# PR9025_B.net
KiCad netlist of a schematic drawn in EAGLE
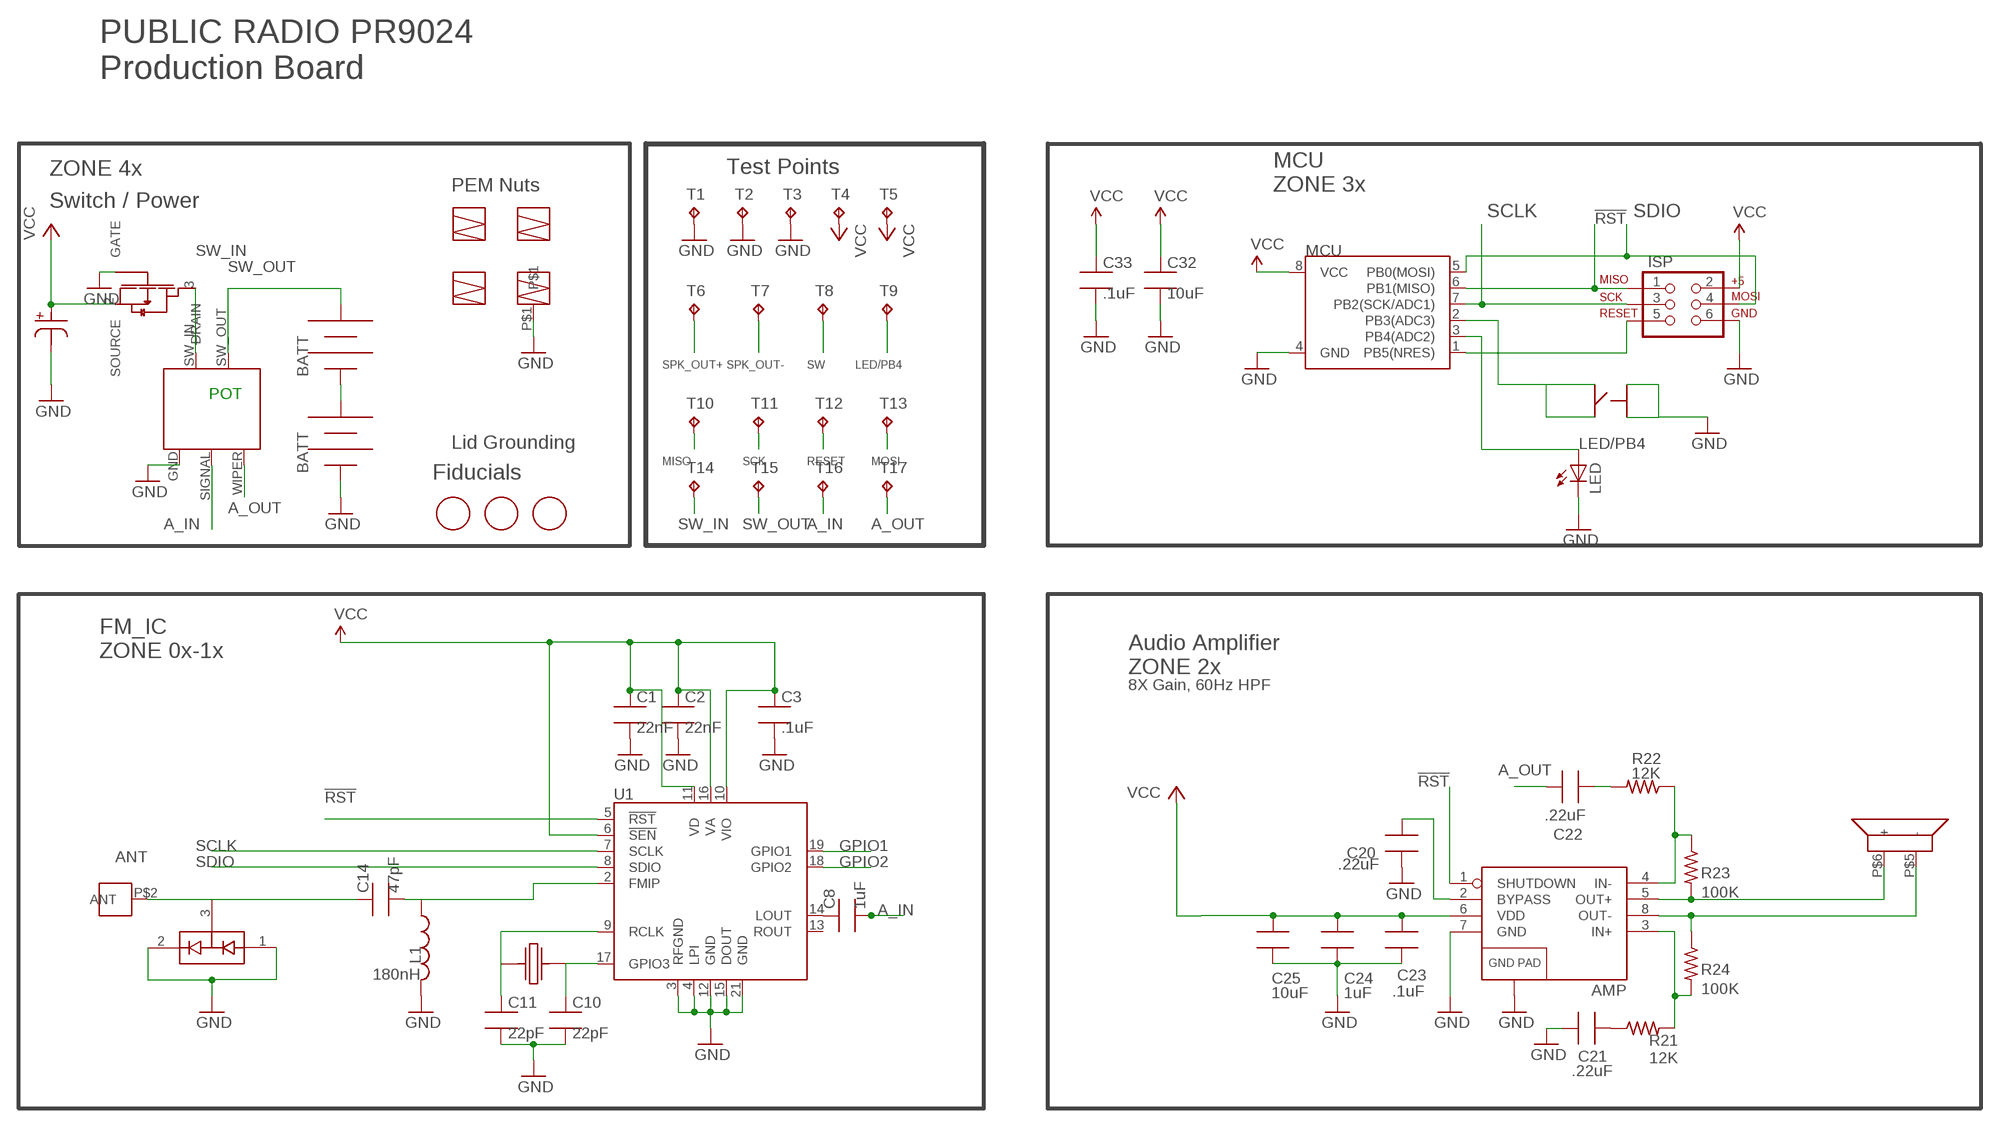
[diagram p0: schematic, sheet 1]

(export (version "E")
  (design (tool "Eeschema 10.0.6"))
  (components
    (comp (ref "AMP")
      (value "TPA6203A1")
      (footprint "eagle-import:8-MSOP")
      (libsource (lib "eagle-import") (part "TPA6203A1"))
    )
    (comp (ref "ANT_MOUNT")
      (value "DNP")
      (footprint "eagle-import:PEM_M3")
      (libsource (lib "eagle-import") (part "M3_PEMNUT"))
    )
    (comp (ref "C1")
      (value "22nF")
      (footprint "eagle-import:0603_CPL")
      (fields
        (field (name "MFG_PN") "CL10B223KB8NNNC")
        (field (name "TOL") "10%")
        (field (name "VOLTAGE") "16V")
      )
      (libsource (lib "eagle-import") (part "C_SMT_0603_CPL"))
    )
    (comp (ref "C2")
      (value "22nF")
      (footprint "eagle-import:0603_CPL")
      (fields
        (field (name "MFG_PN") "CL10B223KB8NNNC")
        (field (name "TOL") "10%")
        (field (name "VOLTAGE") "16V")
      )
      (libsource (lib "eagle-import") (part "C_SMT_0603_CPL"))
    )
    (comp (ref "C3")
      (value ".1uF")
      (footprint "eagle-import:0603_CPL")
      (fields
        (field (name "MFG_PN") "CL10B104KB8SFNC")
        (field (name "TOL") "10%")
        (field (name "VOLTAGE") "16V")
      )
      (libsource (lib "eagle-import") (part "C_SMT_0603_CPL"))
    )
    (comp (ref "C8")
      (value "1uF")
      (footprint "eagle-import:0603_CPL")
      (fields
        (field (name "MFG_PN") "CL10B105KP8NNNC")
        (field (name "TOL") "10%")
        (field (name "VOLTAGE") "10V")
      )
      (libsource (lib "eagle-import") (part "C_SMT_0603_CPL"))
    )
    (comp (ref "C10")
      (value "22pF")
      (footprint "eagle-import:0603_CPL")
      (fields
        (field (name "MFG_PN") "C1608C0G1H220J080AA")
        (field (name "TOL") "5%")
        (field (name "VOLTAGE") "50V")
      )
      (libsource (lib "eagle-import") (part "C_SMT_0603_CPL"))
    )
    (comp (ref "C11")
      (value "22pF")
      (footprint "eagle-import:0603_CPL")
      (fields
        (field (name "MFG_PN") "C1608C0G1H220J080AA")
        (field (name "TOL") "5%")
        (field (name "VOLTAGE") "50V")
      )
      (libsource (lib "eagle-import") (part "C_SMT_0603_CPL"))
    )
    (comp (ref "C14")
      (value "47pF")
      (footprint "eagle-import:0603_CPL")
      (fields
        (field (name "MFG_PN") "CL10C470JB8NCNC")
        (field (name "TOL") "5%")
        (field (name "VOLTAGE") "50V")
      )
      (libsource (lib "eagle-import") (part "C_SMT_0603_CPL"))
    )
    (comp (ref "C20")
      (value ".22uF")
      (footprint "eagle-import:0603_CPL")
      (fields
        (field (name "MFG_PN") "C1608X7R1C224K080AC")
        (field (name "TOL") "10%")
        (field (name "VOLTAGE") "16V")
      )
      (libsource (lib "eagle-import") (part "C_SMT_0603_CPL"))
    )
    (comp (ref "C21")
      (value ".22uF")
      (footprint "eagle-import:0603_CPL")
      (fields
        (field (name "MFG_PN") "C1608X7R1C224K080AC")
        (field (name "TOL") "10%")
        (field (name "VOLTAGE") "16V")
      )
      (libsource (lib "eagle-import") (part "C_SMT_0603_CPL"))
    )
    (comp (ref "C22")
      (value ".22uF")
      (footprint "eagle-import:0603_CPL")
      (fields
        (field (name "MFG_PN") "C1608X7R1C224K080AC")
        (field (name "TOL") "10%")
        (field (name "VOLTAGE") "16V")
      )
      (libsource (lib "eagle-import") (part "C_SMT_0603_CPL"))
    )
    (comp (ref "C23")
      (value ".1uF")
      (footprint "eagle-import:0603_CPL")
      (fields
        (field (name "MFG_PN") "CL10B104KB8SFNC")
        (field (name "TOL") "10%")
        (field (name "VOLTAGE") "16V")
      )
      (libsource (lib "eagle-import") (part "C_SMT_0603_CPL"))
    )
    (comp (ref "C24")
      (value "1uF")
      (footprint "eagle-import:0603_CPL")
      (fields
        (field (name "MFG_PN") "CL10B105KP8NNNC")
        (field (name "TOL") "10%")
        (field (name "VOLTAGE") "10V")
      )
      (libsource (lib "eagle-import") (part "C_SMT_0603_CPL"))
    )
    (comp (ref "C25")
      (value "10uF")
      (footprint "eagle-import:0603_CPL")
      (fields
        (field (name "MFG_PN") "CL10A106MQ8NNNC")
        (field (name "TOL") "20%")
        (field (name "VOLTAGE") "6.3V")
      )
      (libsource (lib "eagle-import") (part "C_SMT_0603_CPL"))
    )
    (comp (ref "C32")
      (value "10uF")
      (footprint "eagle-import:0603_CPL")
      (fields
        (field (name "MFG_PN") "CL10A106MQ8NNNC")
        (field (name "TOL") "20%")
        (field (name "VOLTAGE") "6.3V")
      )
      (libsource (lib "eagle-import") (part "C_SMT_0603_CPL"))
    )
    (comp (ref "C33")
      (value ".1uF")
      (footprint "eagle-import:0603_CPL")
      (fields
        (field (name "MFG_PN") "CL10B104KB8SFNC")
        (field (name "TOL") "10%")
        (field (name "VOLTAGE") "16V")
      )
      (libsource (lib "eagle-import") (part "C_SMT_0603_CPL"))
    )
    (comp (ref "C40")
      (value "220uF")
      (footprint "eagle-import:NICHICON_UD_63")
      (fields (field (name "TOL") "20%") (field (name "VOLTAGE") "16V"))
      (libsource (lib "eagle-import") (part "NICHICON_SERIESUD"))
    )
    (comp (ref "D1")
      (value "BAV99")
      (footprint "eagle-import:SOT23_CPL")
      (fields (field (name "MFG_PN") "BAV99,215"))
      (libsource (lib "eagle-import") (part "BAV99"))
    )
    (comp (ref "FET1")
      (value "AO3435")
      (footprint "eagle-import:SOT23_CPL")
      (fields (field (name "MFG_PN") "AO3435"))
      (libsource (lib "eagle-import") (part "AO3435"))
    )
    (comp (ref "ISP")
      (value "AVR_SPI_PRG_6NS")
      (footprint "eagle-import:2X3-NS")
      (libsource (lib "eagle-import") (part "AVR_SPI_PRG_6NS"))
    )
    (comp (ref "JP5")
      (value "BK-92_MPD_AA_BATT_CLIP")
      (footprint "eagle-import:BK92_AA_BATT")
      (fields (field (name "MFG_PN") "2 of BK92 - supplied by CL Labs"))
      (libsource (lib "eagle-import") (part "BK-92_MPD_AA_BATT_CLIP"))
    )
    (comp (ref "JP6")
      (value "BK-92_MPD_AA_BATT_CLIP")
      (footprint "eagle-import:BK92_AA_BATT")
      (fields (field (name "MFG_PN") "2 of BK92 - supplied by CL Labs"))
      (libsource (lib "eagle-import") (part "BK-92_MPD_AA_BATT_CLIP"))
    )
    (comp (ref "L1")
      (value "180nH")
      (footprint "eagle-import:0805_ADAFRUIT")
      (fields
        (field (name "CURRENT") "400mA")
        (field (name "DCR") "640m")
        (field (name "MFG_PN") "AISC-0805-R18J-T")
        (field (name "TOL") "5%")
      )
      (libsource (lib "eagle-import") (part "L_SMT_0805_ADAFRUIT"))
    )
    (comp (ref "LED")
      (value "HSMC-C265_REVERSE_MOUNT_LED")
      (footprint "eagle-import:HSMC-C265_REVERSE_MOUN_LED")
      (libsource (lib "eagle-import") (part "HSMC-C265_REVERSE_MOUNT_LED"))
    )
    (comp (ref "MARK1")
      (value "FIDUCIAL")
      (footprint "eagle-import:FIDUCIAL_1MM")
      (libsource (lib "eagle-import") (part "FIDUCIAL"))
    )
    (comp (ref "MARK2")
      (value "FIDUCIAL")
      (footprint "eagle-import:FIDUCIAL_1MM")
      (libsource (lib "eagle-import") (part "FIDUCIAL"))
    )
    (comp (ref "MARK3")
      (value "FIDUCIAL")
      (footprint "eagle-import:FIDUCIAL_1MM")
      (libsource (lib "eagle-import") (part "FIDUCIAL"))
    )
    (comp (ref "MCU")
      (value "ATTINY45TINY45-20-SMT")
      (footprint "eagle-import:8-SOIC")
      (libsource (lib "eagle-import") (part "ATTINY45TINY45-20-SMT"))
    )
    (comp (ref "R1")
      (value "VOLUME_POT")
      (footprint "eagle-import:H17112NS_A10K_L20F-002")
      (libsource (lib "eagle-import") (part "VOLUME_POT"))
    )
    (comp (ref "R21")
      (value "12K")
      (footprint "eagle-import:0603_CPL")
      (fields
        (field (name "MFG_PN") "RC0603FR-0712KL")
        (field (name "POWER") "1/10W")
        (field (name "TOL") "1%")
      )
      (libsource (lib "eagle-import") (part "R_SMT_R0603_CPL"))
    )
    (comp (ref "R22")
      (value "12K")
      (footprint "eagle-import:0603_CPL")
      (fields
        (field (name "MFG_PN") "RC0603FR-0712KL")
        (field (name "POWER") "1/10W")
        (field (name "TOL") "1%")
      )
      (libsource (lib "eagle-import") (part "R_SMT_R0603_CPL"))
    )
    (comp (ref "R23")
      (value "100K")
      (footprint "eagle-import:0603_CPL")
      (fields
        (field (name "MFG_PN") "ERJ-3EKF1003V")
        (field (name "POWER") "1/10W")
        (field (name "TOL") "1%")
      )
      (libsource (lib "eagle-import") (part "R_SMT_R0603_CPL"))
    )
    (comp (ref "R24")
      (value "100K")
      (footprint "eagle-import:0603_CPL")
      (fields
        (field (name "MFG_PN") "ERJ-3EKF1003V")
        (field (name "POWER") "1/10W")
        (field (name "TOL") "1%")
      )
      (libsource (lib "eagle-import") (part "R_SMT_R0603_CPL"))
    )
    (comp (ref "SPKR_PLACE")
      (value "DNP")
      (footprint "eagle-import:PR2024_SPKR_PLACE(SMD)")
      (libsource (lib "eagle-import") (part "PR2024_SPKR_SMD"))
    )
    (comp (ref "SW1")
      (value "C&K_PTS645")
      (footprint "eagle-import:C&K_PTS645_SMT")
      (libsource (lib "eagle-import") (part "C&K_PTS645"))
    )
    (comp (ref "T1")
      (value "TPTP20R")
      (footprint "eagle-import:TP20R")
      (libsource (lib "eagle-import") (part "TPTP20R"))
    )
    (comp (ref "T2")
      (value "TPTP20R")
      (footprint "eagle-import:TP20R")
      (libsource (lib "eagle-import") (part "TPTP20R"))
    )
    (comp (ref "T3")
      (value "TPTP20R")
      (footprint "eagle-import:TP20R")
      (libsource (lib "eagle-import") (part "TPTP20R"))
    )
    (comp (ref "T4")
      (value "TPTP20R")
      (footprint "eagle-import:TP20R")
      (libsource (lib "eagle-import") (part "TPTP20R"))
    )
    (comp (ref "T5")
      (value "TPTP20R")
      (footprint "eagle-import:TP20R")
      (libsource (lib "eagle-import") (part "TPTP20R"))
    )
    (comp (ref "T6")
      (value "TPTP20R")
      (footprint "eagle-import:TP20R")
      (libsource (lib "eagle-import") (part "TPTP20R"))
    )
    (comp (ref "T7")
      (value "TPTP20R")
      (footprint "eagle-import:TP20R")
      (libsource (lib "eagle-import") (part "TPTP20R"))
    )
    (comp (ref "T8")
      (value "TPTP20R")
      (footprint "eagle-import:TP20R")
      (libsource (lib "eagle-import") (part "TPTP20R"))
    )
    (comp (ref "T9")
      (value "TPTP20R")
      (footprint "eagle-import:TP20R")
      (libsource (lib "eagle-import") (part "TPTP20R"))
    )
    (comp (ref "T10")
      (value "TPTP20R")
      (footprint "eagle-import:TP20R")
      (libsource (lib "eagle-import") (part "TPTP20R"))
    )
    (comp (ref "T11")
      (value "TPTP20R")
      (footprint "eagle-import:TP20R")
      (libsource (lib "eagle-import") (part "TPTP20R"))
    )
    (comp (ref "T12")
      (value "TPTP20R")
      (footprint "eagle-import:TP20R")
      (libsource (lib "eagle-import") (part "TPTP20R"))
    )
    (comp (ref "T13")
      (value "TPTP20R")
      (footprint "eagle-import:TP20R")
      (libsource (lib "eagle-import") (part "TPTP20R"))
    )
    (comp (ref "T14")
      (value "TPTP20R")
      (footprint "eagle-import:TP20R")
      (libsource (lib "eagle-import") (part "TPTP20R"))
    )
    (comp (ref "T15")
      (value "TPTP20R")
      (footprint "eagle-import:TP20R")
      (libsource (lib "eagle-import") (part "TPTP20R"))
    )
    (comp (ref "T16")
      (value "TPTP20R")
      (footprint "eagle-import:TP20R")
      (libsource (lib "eagle-import") (part "TPTP20R"))
    )
    (comp (ref "T17")
      (value "TPTP20R")
      (footprint "eagle-import:TP20R")
      (libsource (lib "eagle-import") (part "TPTP20R"))
    )
    (comp (ref "U$2")
      (value "PEM_SMT")
      (footprint "eagle-import:PEM_SMT")
      (libsource (lib "eagle-import") (part "PEM_SMT"))
    )
    (comp (ref "U$3")
      (value "PEM_SMT")
      (footprint "eagle-import:PEM_SMT")
      (libsource (lib "eagle-import") (part "PEM_SMT"))
    )
    (comp (ref "U$4")
      (value "PEM_SMT")
      (footprint "eagle-import:PEM_SMT")
      (libsource (lib "eagle-import") (part "PEM_SMT"))
    )
    (comp (ref "U$5")
      (value "PEM_M3_SMT_W/PIN")
      (footprint "eagle-import:PEM_SMT")
      (libsource (lib "eagle-import") (part "PEM_M3_SMT_W/PIN"))
    )
    (comp (ref "U1")
      (value "SI4702-C19-GMR")
      (footprint "eagle-import:SI470X_20_QFN")
      (fields (field (name "MFG_PN") "Si4702 C19 GM - supplied by CL Labs"))
      (libsource (lib "eagle-import") (part "SI4702-C19-GMR"))
    )
    (comp (ref "X1")
      (value "ABS25XTAL")
      (footprint "eagle-import:4-SOJ")
      (libsource (lib "eagle-import") (part "ABS25XTAL"))
    )
  )
  (nets
    (net (code "1") (name "/ANT") (class "Default")
      (node (ref "ANT_MOUNT") (pin "P$2") (pinfunction "ANT_P$2") (pintype "bidirectional"))
      (node (ref "C14") (pin "1") (pinfunction "1_1") (pintype "passive"))
      (node (ref "D1") (pin "3") (pinfunction "COM_3") (pintype "bidirectional"))
    )
    (net (code "2") (name "/A_IN") (class "Default")
      (node (ref "C8") (pin "2") (pinfunction "2_2") (pintype "passive"))
      (node (ref "R1") (pin "SIGNAL") (pinfunction "SIGNAL_SIGNAL") (pintype "bidirectional"))
      (node (ref "T16") (pin "TP") (pinfunction "TP_TP") (pintype "input"))
    )
    (net (code "3") (name "/A_OUT") (class "Default")
      (node (ref "C22") (pin "2") (pinfunction "2_2") (pintype "passive"))
      (node (ref "R1") (pin "WIPER") (pinfunction "WIPER_WIPER") (pintype "bidirectional"))
      (node (ref "T17") (pin "TP") (pinfunction "TP_TP") (pintype "input"))
    )
    (net (code "4") (name "/GPIO1") (class "Default")
      (node (ref "U1") (pin "19") (pinfunction "GPIO1_19") (pintype "bidirectional"))
    )
    (net (code "5") (name "/GPIO2") (class "Default")
      (node (ref "U1") (pin "18") (pinfunction "GPIO2_18") (pintype "bidirectional"))
    )
    (net (code "6") (name "/LED{slash}PB4") (class "Default")
      (node (ref "LED") (pin "P$1") (pinfunction "A_P$1") (pintype "passive"))
      (node (ref "MCU") (pin "3") (pinfunction "PB4(ADC2)_3") (pintype "bidirectional"))
      (node (ref "T9") (pin "TP") (pinfunction "TP_TP") (pintype "input"))
    )
    (net (code "7") (name "/RESET") (class "Default")
      (node (ref "ISP") (pin "5") (pinfunction "5_5") (pintype "passive"))
      (node (ref "MCU") (pin "1") (pinfunction "PB5(NRES)_1") (pintype "bidirectional"))
      (node (ref "T12") (pin "TP") (pinfunction "TP_TP") (pintype "input"))
    )
    (net (code "8") (name "/SCLK") (class "Default")
      (node (ref "ISP") (pin "3") (pinfunction "3_3") (pintype "passive"))
      (node (ref "MCU") (pin "7") (pinfunction "PB2(SCK/ADC1)_7") (pintype "bidirectional"))
      (node (ref "T11") (pin "TP") (pinfunction "TP_TP") (pintype "input"))
      (node (ref "U1") (pin "7") (pinfunction "SCLK_7") (pintype "bidirectional"))
    )
    (net (code "9") (name "/SDIO") (class "Default")
      (node (ref "ISP") (pin "4") (pinfunction "4_4") (pintype "passive"))
      (node (ref "MCU") (pin "5") (pinfunction "PB0(MOSI)_5") (pintype "bidirectional"))
      (node (ref "T13") (pin "TP") (pinfunction "TP_TP") (pintype "input"))
      (node (ref "U1") (pin "8") (pinfunction "SDIO_8") (pintype "bidirectional"))
    )
    (net (code "10") (name "/SPK_OUT+") (class "Default")
      (node (ref "AMP") (pin "5") (pinfunction "OUT+_5") (pintype "bidirectional"))
      (node (ref "R23") (pin "2") (pinfunction "2_2") (pintype "passive"))
      (node (ref "SPKR_PLACE") (pin "P$6") (pinfunction "+_P$6") (pintype "bidirectional"))
      (node (ref "T6") (pin "TP") (pinfunction "TP_TP") (pintype "input"))
    )
    (net (code "11") (name "/SPK_OUT-") (class "Default")
      (node (ref "AMP") (pin "8") (pinfunction "OUT-_8") (pintype "bidirectional"))
      (node (ref "R24") (pin "1") (pinfunction "1_1") (pintype "passive"))
      (node (ref "SPKR_PLACE") (pin "P$5") (pinfunction "-_P$5") (pintype "bidirectional"))
      (node (ref "T7") (pin "TP") (pinfunction "TP_TP") (pintype "input"))
    )
    (net (code "12") (name "/SW") (class "Default")
      (node (ref "MCU") (pin "2") (pinfunction "PB3(ADC3)_2") (pintype "bidirectional"))
      (node (ref "SW1") (pin "P$3") (pinfunction "P$3_P$3") (pintype "bidirectional"))
      (node (ref "SW1") (pin "P$4") (pinfunction "P$4_P$4") (pintype "bidirectional"))
      (node (ref "T8") (pin "TP") (pinfunction "TP_TP") (pintype "input"))
    )
    (net (code "13") (name "/SW_IN") (class "Default")
      (node (ref "FET1") (pin "3") (pinfunction "DRAIN_3") (pintype "bidirectional"))
      (node (ref "R1") (pin "SW_IN") (pinfunction "SW_IN_SW_IN") (pintype "bidirectional"))
      (node (ref "T14") (pin "TP") (pinfunction "TP_TP") (pintype "input"))
    )
    (net (code "14") (name "/SW_OUT") (class "Default")
      (node (ref "JP5") (pin "POS") (pinfunction "POS_POS") (pintype "bidirectional"))
      (node (ref "JP5") (pin "POS@2") (pinfunction "POS_POS@2") (pintype "bidirectional"))
      (node (ref "R1") (pin "SW_OUT") (pinfunction "SW_OUT_SW_OUT") (pintype "bidirectional"))
      (node (ref "T15") (pin "TP") (pinfunction "TP_TP") (pintype "input"))
    )
    (net (code "15") (name "/~{RST}") (class "Default")
      (node (ref "AMP") (pin "1") (pinfunction "SHUTDOWN_1") (pintype "input"))
      (node (ref "ISP") (pin "1") (pinfunction "1_1") (pintype "passive"))
      (node (ref "MCU") (pin "6") (pinfunction "PB1(MISO)_6") (pintype "bidirectional"))
      (node (ref "T10") (pin "TP") (pinfunction "TP_TP") (pintype "input"))
      (node (ref "U1") (pin "5") (pinfunction "~{RST}_5") (pintype "bidirectional"))
    )
    (net (code "16") (name "GND") (class "Default")
      (node (ref "AMP") (pin "7") (pinfunction "GND_7") (pintype "power_in"))
      (node (ref "AMP") (pin "9") (pinfunction "GND_9") (pintype "power_in"))
      (node (ref "C1") (pin "2") (pinfunction "2_2") (pintype "passive"))
      (node (ref "C10") (pin "2") (pinfunction "2_2") (pintype "passive"))
      (node (ref "C11") (pin "2") (pinfunction "2_2") (pintype "passive"))
      (node (ref "C2") (pin "2") (pinfunction "2_2") (pintype "passive"))
      (node (ref "C20") (pin "1") (pinfunction "1_1") (pintype "passive"))
      (node (ref "C21") (pin "1") (pinfunction "1_1") (pintype "passive"))
      (node (ref "C23") (pin "2") (pinfunction "2_2") (pintype "passive"))
      (node (ref "C24") (pin "2") (pinfunction "2_2") (pintype "passive"))
      (node (ref "C25") (pin "2") (pinfunction "2_2") (pintype "passive"))
      (node (ref "C3") (pin "2") (pinfunction "2_2") (pintype "passive"))
      (node (ref "C32") (pin "2") (pinfunction "2_2") (pintype "passive"))
      (node (ref "C33") (pin "2") (pinfunction "2_2") (pintype "passive"))
      (node (ref "C40") (pin "P$2") (pinfunction "P$2_P$2") (pintype "bidirectional"))
      (node (ref "D1") (pin "1") (pinfunction "A1_1") (pintype "bidirectional"))
      (node (ref "D1") (pin "2") (pinfunction "C2_2") (pintype "bidirectional"))
      (node (ref "FET1") (pin "1") (pinfunction "GATE_1") (pintype "bidirectional"))
      (node (ref "ISP") (pin "6") (pinfunction "6_6") (pintype "passive"))
      (node (ref "JP6") (pin "NEG") (pinfunction "NEG_NEG") (pintype "bidirectional"))
      (node (ref "JP6") (pin "NEG@2") (pinfunction "NEG_NEG@2") (pintype "bidirectional"))
      (node (ref "L1") (pin "2") (pinfunction "2_2") (pintype "passive"))
      (node (ref "LED") (pin "P$2") (pinfunction "C_P$2") (pintype "passive"))
      (node (ref "MCU") (pin "4") (pinfunction "GND_4") (pintype "bidirectional"))
      (node (ref "R1") (pin "GND") (pinfunction "GND_GND") (pintype "bidirectional"))
      (node (ref "SW1") (pin "P$1") (pinfunction "P$1_P$1") (pintype "bidirectional"))
      (node (ref "SW1") (pin "P$2") (pinfunction "P$2_P$2") (pintype "bidirectional"))
      (node (ref "T1") (pin "TP") (pinfunction "TP_TP") (pintype "input"))
      (node (ref "T2") (pin "TP") (pinfunction "TP_TP") (pintype "input"))
      (node (ref "T3") (pin "TP") (pinfunction "TP_TP") (pintype "input"))
      (node (ref "U$5") (pin "P$1") (pinfunction "P$1_P$1") (pintype "bidirectional"))
      (node (ref "U1") (pin "12") (pinfunction "GND_12") (pintype "bidirectional"))
      (node (ref "U1") (pin "15") (pinfunction "DOUT_15") (pintype "bidirectional"))
      (node (ref "U1") (pin "21") (pinfunction "GND_21") (pintype "bidirectional"))
      (node (ref "U1") (pin "3") (pinfunction "RFGND_3") (pintype "bidirectional"))
      (node (ref "U1") (pin "4") (pinfunction "LPI_4") (pintype "bidirectional"))
    )
    (net (code "17") (name "Net-(AMP-BYPASS)") (class "Default")
      (node (ref "AMP") (pin "2") (pinfunction "BYPASS_2") (pintype "bidirectional"))
      (node (ref "C20") (pin "2") (pinfunction "2_2") (pintype "passive"))
    )
    (net (code "18") (name "Net-(AMP-IN+)") (class "Default")
      (node (ref "AMP") (pin "3") (pinfunction "IN+_3") (pintype "bidirectional"))
      (node (ref "R21") (pin "2") (pinfunction "2_2") (pintype "passive"))
      (node (ref "R24") (pin "2") (pinfunction "2_2") (pintype "passive"))
    )
    (net (code "19") (name "Net-(AMP-IN-)") (class "Default")
      (node (ref "AMP") (pin "4") (pinfunction "IN-_4") (pintype "bidirectional"))
      (node (ref "R22") (pin "1") (pinfunction "1_1") (pintype "passive"))
      (node (ref "R23") (pin "1") (pinfunction "1_1") (pintype "passive"))
    )
    (net (code "20") (name "Net-(C21-Pad2)") (class "Default")
      (node (ref "C21") (pin "2") (pinfunction "2_2") (pintype "passive"))
      (node (ref "R21") (pin "1") (pinfunction "1_1") (pintype "passive"))
    )
    (net (code "21") (name "Net-(C22-Pad1)") (class "Default")
      (node (ref "C22") (pin "1") (pinfunction "1_1") (pintype "passive"))
      (node (ref "R22") (pin "2") (pinfunction "2_2") (pintype "passive"))
    )
    (net (code "22") (name "Net-(JP5-NEG-PadNEG@2)") (class "Default")
      (node (ref "JP5") (pin "NEG") (pinfunction "NEG_NEG") (pintype "bidirectional"))
      (node (ref "JP5") (pin "NEG@2") (pinfunction "NEG_NEG@2") (pintype "bidirectional"))
      (node (ref "JP6") (pin "POS") (pinfunction "POS_POS") (pintype "bidirectional"))
      (node (ref "JP6") (pin "POS@2") (pinfunction "POS_POS@2") (pintype "bidirectional"))
    )
    (net (code "23") (name "Net-(U1-FMIP)") (class "Default")
      (node (ref "C14") (pin "2") (pinfunction "2_2") (pintype "passive"))
      (node (ref "L1") (pin "1") (pinfunction "1_1") (pintype "passive"))
      (node (ref "U1") (pin "2") (pinfunction "FMIP_2") (pintype "bidirectional"))
    )
    (net (code "24") (name "Net-(U1-GPIO3)") (class "Default")
      (node (ref "C10") (pin "1") (pinfunction "1_1") (pintype "passive"))
      (node (ref "U1") (pin "17") (pinfunction "GPIO3_17") (pintype "bidirectional"))
      (node (ref "X1") (pin "P$4") (pinfunction "P$4_P$4") (pintype "bidirectional"))
    )
    (net (code "25") (name "Net-(U1-LOUT)") (class "Default")
      (node (ref "C8") (pin "1") (pinfunction "1_1") (pintype "passive"))
      (node (ref "U1") (pin "14") (pinfunction "LOUT_14") (pintype "bidirectional"))
    )
    (net (code "26") (name "Net-(U1-RCLK)") (class "Default")
      (node (ref "C11") (pin "1") (pinfunction "1_1") (pintype "passive"))
      (node (ref "U1") (pin "9") (pinfunction "RCLK_9") (pintype "bidirectional"))
      (node (ref "X1") (pin "P$1") (pinfunction "P$1_P$1") (pintype "bidirectional"))
    )
    (net (code "27") (name "VCC") (class "Default")
      (node (ref "AMP") (pin "6") (pinfunction "VDD_6") (pintype "power_in"))
      (node (ref "C1") (pin "1") (pinfunction "1_1") (pintype "passive"))
      (node (ref "C2") (pin "1") (pinfunction "1_1") (pintype "passive"))
      (node (ref "C23") (pin "1") (pinfunction "1_1") (pintype "passive"))
      (node (ref "C24") (pin "1") (pinfunction "1_1") (pintype "passive"))
      (node (ref "C25") (pin "1") (pinfunction "1_1") (pintype "passive"))
      (node (ref "C3") (pin "1") (pinfunction "1_1") (pintype "passive"))
      (node (ref "C32") (pin "1") (pinfunction "1_1") (pintype "passive"))
      (node (ref "C33") (pin "1") (pinfunction "1_1") (pintype "passive"))
      (node (ref "C40") (pin "P$1") (pinfunction "P$1_P$1") (pintype "bidirectional"))
      (node (ref "FET1") (pin "2") (pinfunction "SOURCE_2") (pintype "bidirectional"))
      (node (ref "ISP") (pin "2") (pinfunction "2_2") (pintype "passive"))
      (node (ref "MCU") (pin "8") (pinfunction "VCC_8") (pintype "bidirectional"))
      (node (ref "T4") (pin "TP") (pinfunction "TP_TP") (pintype "input"))
      (node (ref "T5") (pin "TP") (pinfunction "TP_TP") (pintype "input"))
      (node (ref "U1") (pin "10") (pinfunction "VIO_10") (pintype "bidirectional"))
      (node (ref "U1") (pin "11") (pinfunction "VD_11") (pintype "bidirectional"))
      (node (ref "U1") (pin "16") (pinfunction "VA_16") (pintype "bidirectional"))
      (node (ref "U1") (pin "6") (pinfunction "~{SEN}_6") (pintype "bidirectional"))
    )
    (net (code "28") (name "unconnected-(U1-ROUT-Pad13)") (class "Default")
      (node (ref "U1") (pin "13") (pinfunction "ROUT_13") (pintype "bidirectional"))
    )
  )
)
